# input.net
KiCad netlist of a schematic drawn in Altium Designer
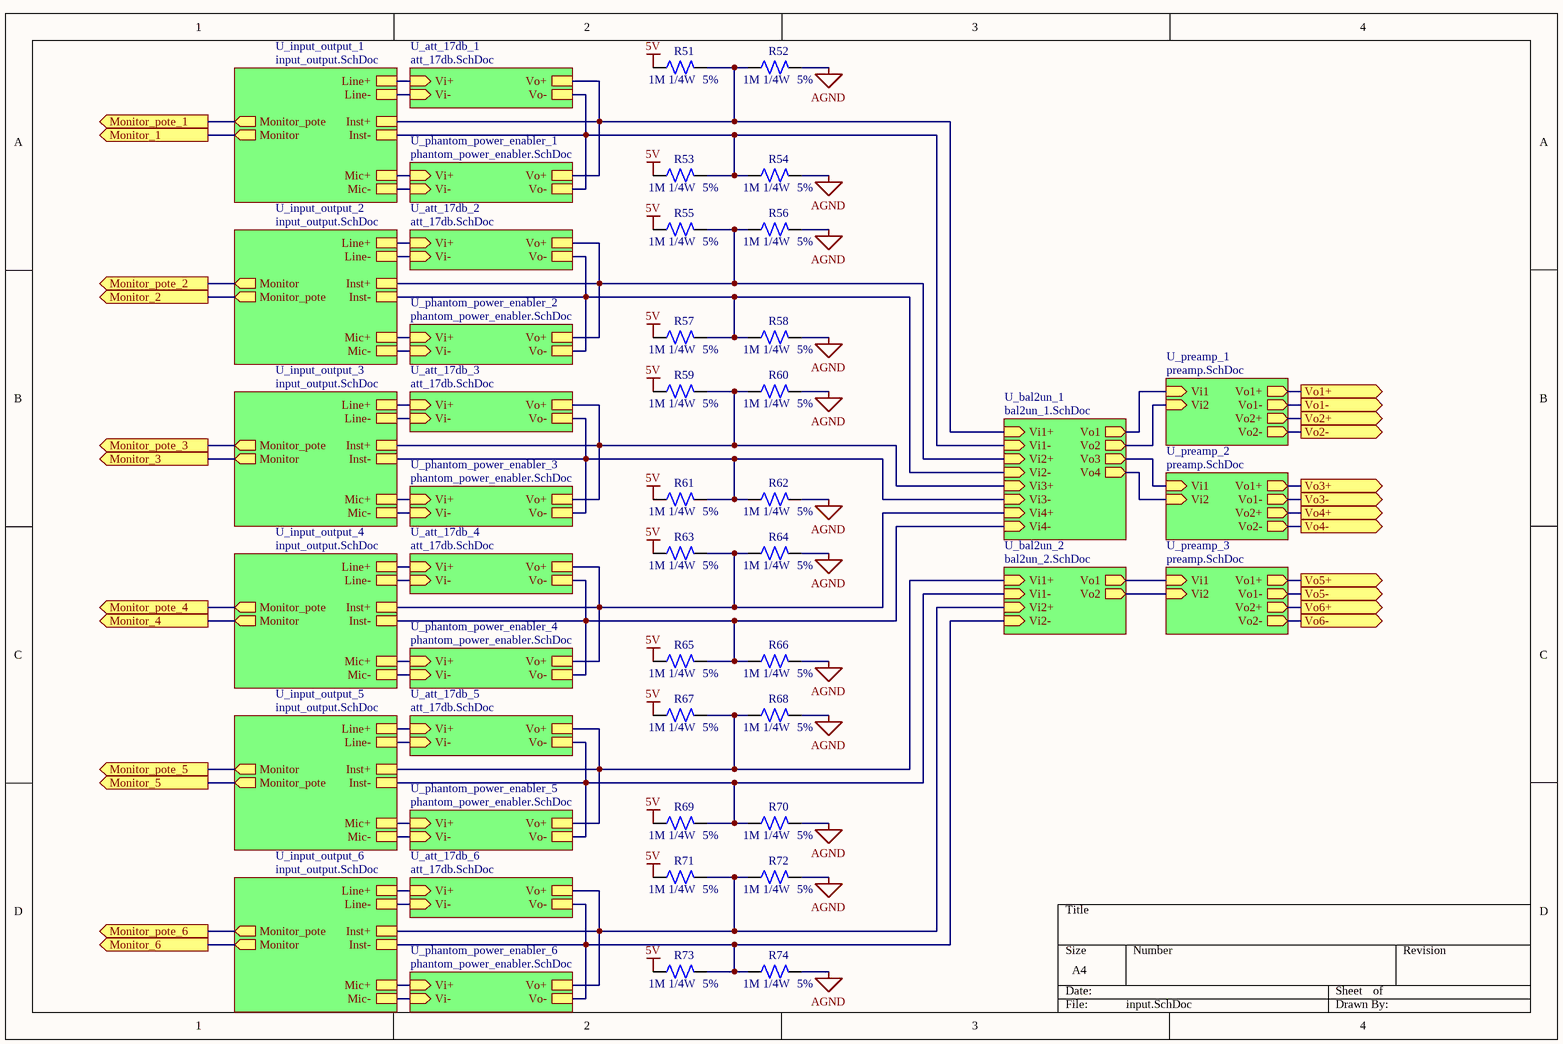
[diagram p0: input.SchDoc]

(export (version "E")
  (design (tool "Eeschema 10.0.6"))
  (components
    (comp (ref "R51")
      (value "Resistor")
      (footprint "R0805")
      (description "Resistencia")
      (fields (field (name "VALOR") "1M") (field (name "POTENCIA") "1/4W") (field (name "TOLERANCIA") "5%"))
      (libsource (lib "sch_comunes") (part "Resistor"))
    )
    (comp (ref "R52")
      (value "Resistor")
      (footprint "R0805")
      (description "Resistencia")
      (fields (field (name "VALOR") "1M") (field (name "POTENCIA") "1/4W") (field (name "TOLERANCIA") "5%"))
      (libsource (lib "sch_comunes") (part "Resistor"))
    )
    (comp (ref "R53")
      (value "Resistor")
      (footprint "R0805")
      (description "Resistencia")
      (fields (field (name "VALOR") "1M") (field (name "POTENCIA") "1/4W") (field (name "TOLERANCIA") "5%"))
      (libsource (lib "sch_comunes") (part "Resistor"))
    )
    (comp (ref "R54")
      (value "Resistor")
      (footprint "R0805")
      (description "Resistencia")
      (fields (field (name "VALOR") "1M") (field (name "POTENCIA") "1/4W") (field (name "TOLERANCIA") "5%"))
      (libsource (lib "sch_comunes") (part "Resistor"))
    )
    (comp (ref "R55")
      (value "Resistor")
      (footprint "R0805")
      (description "Resistencia")
      (fields (field (name "VALOR") "1M") (field (name "POTENCIA") "1/4W") (field (name "TOLERANCIA") "5%"))
      (libsource (lib "sch_comunes") (part "Resistor"))
    )
    (comp (ref "R56")
      (value "Resistor")
      (footprint "R0805")
      (description "Resistencia")
      (fields (field (name "VALOR") "1M") (field (name "POTENCIA") "1/4W") (field (name "TOLERANCIA") "5%"))
      (libsource (lib "sch_comunes") (part "Resistor"))
    )
    (comp (ref "R57")
      (value "Resistor")
      (footprint "R0805")
      (description "Resistencia")
      (fields (field (name "VALOR") "1M") (field (name "POTENCIA") "1/4W") (field (name "TOLERANCIA") "5%"))
      (libsource (lib "sch_comunes") (part "Resistor"))
    )
    (comp (ref "R58")
      (value "Resistor")
      (footprint "R0805")
      (description "Resistencia")
      (fields (field (name "VALOR") "1M") (field (name "POTENCIA") "1/4W") (field (name "TOLERANCIA") "5%"))
      (libsource (lib "sch_comunes") (part "Resistor"))
    )
    (comp (ref "R59")
      (value "Resistor")
      (footprint "R0805")
      (description "Resistencia")
      (fields (field (name "VALOR") "1M") (field (name "POTENCIA") "1/4W") (field (name "TOLERANCIA") "5%"))
      (libsource (lib "sch_comunes") (part "Resistor"))
    )
    (comp (ref "R60")
      (value "Resistor")
      (footprint "R0805")
      (description "Resistencia")
      (fields (field (name "VALOR") "1M") (field (name "POTENCIA") "1/4W") (field (name "TOLERANCIA") "5%"))
      (libsource (lib "sch_comunes") (part "Resistor"))
    )
    (comp (ref "R61")
      (value "Resistor")
      (footprint "R0805")
      (description "Resistencia")
      (fields (field (name "VALOR") "1M") (field (name "POTENCIA") "1/4W") (field (name "TOLERANCIA") "5%"))
      (libsource (lib "sch_comunes") (part "Resistor"))
    )
    (comp (ref "R62")
      (value "Resistor")
      (footprint "R0805")
      (description "Resistencia")
      (fields (field (name "VALOR") "1M") (field (name "POTENCIA") "1/4W") (field (name "TOLERANCIA") "5%"))
      (libsource (lib "sch_comunes") (part "Resistor"))
    )
    (comp (ref "R63")
      (value "Resistor")
      (footprint "R0805")
      (description "Resistencia")
      (fields (field (name "VALOR") "1M") (field (name "POTENCIA") "1/4W") (field (name "TOLERANCIA") "5%"))
      (libsource (lib "sch_comunes") (part "Resistor"))
    )
    (comp (ref "R64")
      (value "Resistor")
      (footprint "R0805")
      (description "Resistencia")
      (fields (field (name "VALOR") "1M") (field (name "POTENCIA") "1/4W") (field (name "TOLERANCIA") "5%"))
      (libsource (lib "sch_comunes") (part "Resistor"))
    )
    (comp (ref "R65")
      (value "Resistor")
      (footprint "R0805")
      (description "Resistencia")
      (fields (field (name "VALOR") "1M") (field (name "POTENCIA") "1/4W") (field (name "TOLERANCIA") "5%"))
      (libsource (lib "sch_comunes") (part "Resistor"))
    )
    (comp (ref "R66")
      (value "Resistor")
      (footprint "R0805")
      (description "Resistencia")
      (fields (field (name "VALOR") "1M") (field (name "POTENCIA") "1/4W") (field (name "TOLERANCIA") "5%"))
      (libsource (lib "sch_comunes") (part "Resistor"))
    )
    (comp (ref "R67")
      (value "Resistor")
      (footprint "R0805")
      (description "Resistencia")
      (fields (field (name "VALOR") "1M") (field (name "POTENCIA") "1/4W") (field (name "TOLERANCIA") "5%"))
      (libsource (lib "sch_comunes") (part "Resistor"))
    )
    (comp (ref "R68")
      (value "Resistor")
      (footprint "R0805")
      (description "Resistencia")
      (fields (field (name "VALOR") "1M") (field (name "POTENCIA") "1/4W") (field (name "TOLERANCIA") "5%"))
      (libsource (lib "sch_comunes") (part "Resistor"))
    )
    (comp (ref "R69")
      (value "Resistor")
      (footprint "R0805")
      (description "Resistencia")
      (fields (field (name "VALOR") "1M") (field (name "POTENCIA") "1/4W") (field (name "TOLERANCIA") "5%"))
      (libsource (lib "sch_comunes") (part "Resistor"))
    )
    (comp (ref "R70")
      (value "Resistor")
      (footprint "R0805")
      (description "Resistencia")
      (fields (field (name "VALOR") "1M") (field (name "POTENCIA") "1/4W") (field (name "TOLERANCIA") "5%"))
      (libsource (lib "sch_comunes") (part "Resistor"))
    )
    (comp (ref "R71")
      (value "Resistor")
      (footprint "R0805")
      (description "Resistencia")
      (fields (field (name "VALOR") "1M") (field (name "POTENCIA") "1/4W") (field (name "TOLERANCIA") "5%"))
      (libsource (lib "sch_comunes") (part "Resistor"))
    )
    (comp (ref "R72")
      (value "Resistor")
      (footprint "R0805")
      (description "Resistencia")
      (fields (field (name "VALOR") "1M") (field (name "POTENCIA") "1/4W") (field (name "TOLERANCIA") "5%"))
      (libsource (lib "sch_comunes") (part "Resistor"))
    )
    (comp (ref "R73")
      (value "Resistor")
      (footprint "R0805")
      (description "Resistencia")
      (fields (field (name "VALOR") "1M") (field (name "POTENCIA") "1/4W") (field (name "TOLERANCIA") "5%"))
      (libsource (lib "sch_comunes") (part "Resistor"))
    )
    (comp (ref "R74")
      (value "Resistor")
      (footprint "R0805")
      (description "Resistencia")
      (fields (field (name "VALOR") "1M") (field (name "POTENCIA") "1/4W") (field (name "TOLERANCIA") "5%"))
      (libsource (lib "sch_comunes") (part "Resistor"))
    )
  )
  (nets
    (net (code "1") (name "/Inst+") (class "Default")
      (node (ref "R63") (pin "2") (pinfunction "2_2") (pintype "passive"))
      (node (ref "R64") (pin "1") (pinfunction "1_1") (pintype "passive"))
    )
    (net (code "2") (name "/Inst+_1") (class "Default")
      (node (ref "R51") (pin "2") (pinfunction "2_2") (pintype "passive"))
      (node (ref "R52") (pin "1") (pinfunction "1_1") (pintype "passive"))
    )
    (net (code "3") (name "/Inst+_2") (class "Default")
      (node (ref "R55") (pin "2") (pinfunction "2_2") (pintype "passive"))
      (node (ref "R56") (pin "1") (pinfunction "1_1") (pintype "passive"))
    )
    (net (code "4") (name "/Inst+_3") (class "Default")
      (node (ref "R67") (pin "2") (pinfunction "2_2") (pintype "passive"))
      (node (ref "R68") (pin "1") (pinfunction "1_1") (pintype "passive"))
    )
    (net (code "5") (name "/Inst+_4") (class "Default")
      (node (ref "R71") (pin "2") (pinfunction "2_2") (pintype "passive"))
      (node (ref "R72") (pin "1") (pinfunction "1_1") (pintype "passive"))
    )
    (net (code "6") (name "/Inst+_5") (class "Default")
      (node (ref "R59") (pin "2") (pinfunction "2_2") (pintype "passive"))
      (node (ref "R60") (pin "1") (pinfunction "1_1") (pintype "passive"))
    )
    (net (code "7") (name "/Inst-") (class "Default")
      (node (ref "R65") (pin "2") (pinfunction "2_2") (pintype "passive"))
      (node (ref "R66") (pin "1") (pinfunction "1_1") (pintype "passive"))
    )
    (net (code "8") (name "/Inst-_1") (class "Default")
      (node (ref "R57") (pin "2") (pinfunction "2_2") (pintype "passive"))
      (node (ref "R58") (pin "1") (pinfunction "1_1") (pintype "passive"))
    )
    (net (code "9") (name "/Inst-_2") (class "Default")
      (node (ref "R53") (pin "2") (pinfunction "2_2") (pintype "passive"))
      (node (ref "R54") (pin "1") (pinfunction "1_1") (pintype "passive"))
    )
    (net (code "10") (name "/Inst-_3") (class "Default")
      (node (ref "R69") (pin "2") (pinfunction "2_2") (pintype "passive"))
      (node (ref "R70") (pin "1") (pinfunction "1_1") (pintype "passive"))
    )
    (net (code "11") (name "/Inst-_4") (class "Default")
      (node (ref "R73") (pin "2") (pinfunction "2_2") (pintype "passive"))
      (node (ref "R74") (pin "1") (pinfunction "1_1") (pintype "passive"))
    )
    (net (code "12") (name "/Inst-_5") (class "Default")
      (node (ref "R61") (pin "2") (pinfunction "2_2") (pintype "passive"))
      (node (ref "R62") (pin "1") (pinfunction "1_1") (pintype "passive"))
    )
    (net (code "67") (name "5V") (class "Default")
      (node (ref "R51") (pin "1") (pinfunction "1_1") (pintype "passive"))
      (node (ref "R53") (pin "1") (pinfunction "1_1") (pintype "passive"))
      (node (ref "R55") (pin "1") (pinfunction "1_1") (pintype "passive"))
      (node (ref "R57") (pin "1") (pinfunction "1_1") (pintype "passive"))
      (node (ref "R59") (pin "1") (pinfunction "1_1") (pintype "passive"))
      (node (ref "R61") (pin "1") (pinfunction "1_1") (pintype "passive"))
      (node (ref "R63") (pin "1") (pinfunction "1_1") (pintype "passive"))
      (node (ref "R65") (pin "1") (pinfunction "1_1") (pintype "passive"))
      (node (ref "R67") (pin "1") (pinfunction "1_1") (pintype "passive"))
      (node (ref "R69") (pin "1") (pinfunction "1_1") (pintype "passive"))
      (node (ref "R71") (pin "1") (pinfunction "1_1") (pintype "passive"))
      (node (ref "R73") (pin "1") (pinfunction "1_1") (pintype "passive"))
    )
    (net (code "68") (name "AGND") (class "Default")
      (node (ref "R52") (pin "2") (pinfunction "2_2") (pintype "passive"))
      (node (ref "R54") (pin "2") (pinfunction "2_2") (pintype "passive"))
      (node (ref "R56") (pin "2") (pinfunction "2_2") (pintype "passive"))
      (node (ref "R58") (pin "2") (pinfunction "2_2") (pintype "passive"))
      (node (ref "R60") (pin "2") (pinfunction "2_2") (pintype "passive"))
      (node (ref "R62") (pin "2") (pinfunction "2_2") (pintype "passive"))
      (node (ref "R64") (pin "2") (pinfunction "2_2") (pintype "passive"))
      (node (ref "R66") (pin "2") (pinfunction "2_2") (pintype "passive"))
      (node (ref "R68") (pin "2") (pinfunction "2_2") (pintype "passive"))
      (node (ref "R70") (pin "2") (pinfunction "2_2") (pintype "passive"))
      (node (ref "R72") (pin "2") (pinfunction "2_2") (pintype "passive"))
      (node (ref "R74") (pin "2") (pinfunction "2_2") (pintype "passive"))
    )
  )
)
